# Hoov_Fuzz.net
KiCad netlist of a schematic drawn in EAGLE
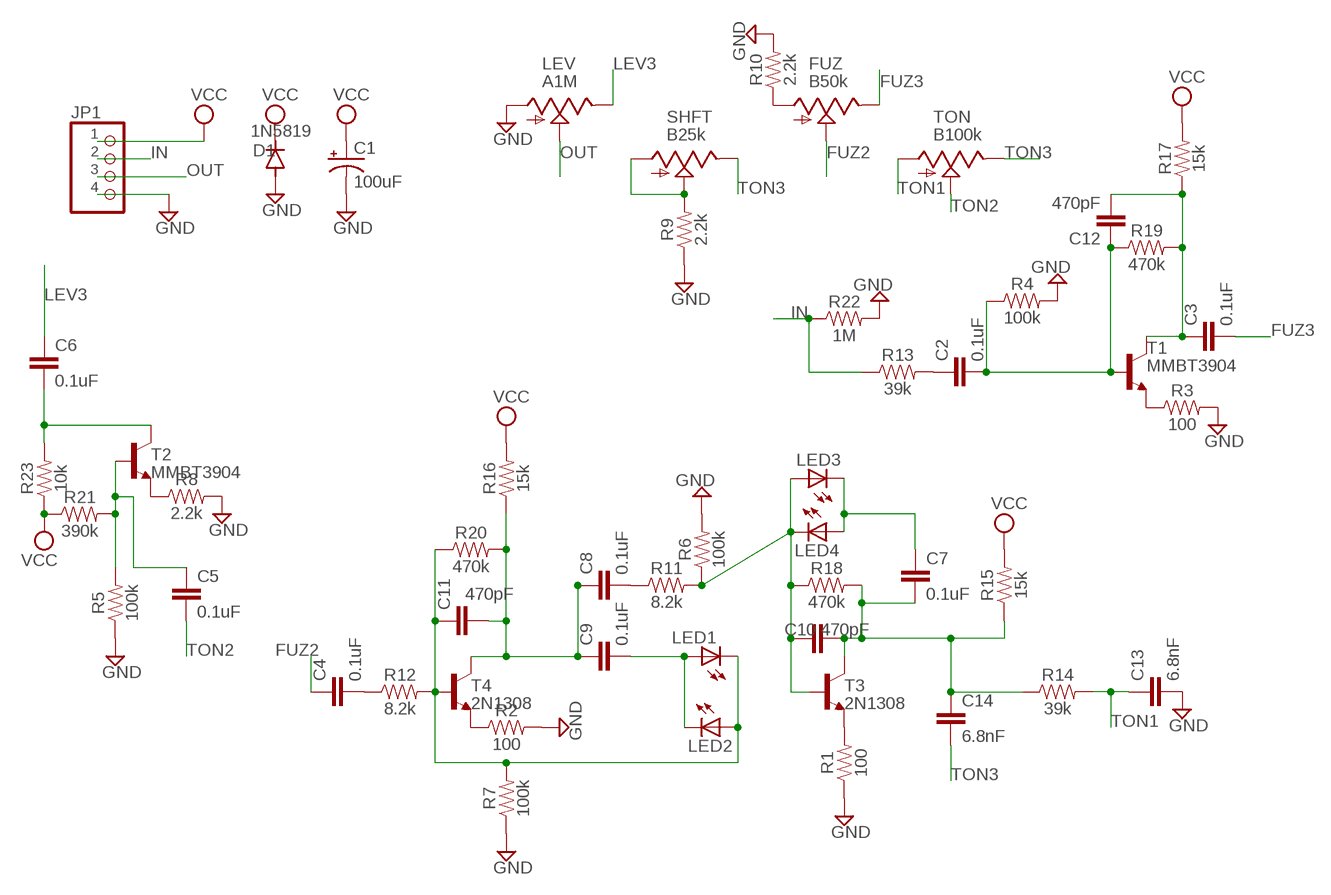
[diagram p0: schematic, sheet 1]

(export (version "E")
  (design (tool "Eeschema 10.0.6"))
  (components
    (comp (ref "C1")
      (value "100uF")
      (footprint "eagle-import:PAN_B_SMD+THRU")
      (libsource (lib "eagle-import") (part "CAP_SMD+THRUPAN_B"))
    )
    (comp (ref "C2")
      (value "0.1uF")
      (footprint "eagle-import:0603")
      (libsource (lib "eagle-import") (part "0.1UF-0603-25V-(+80/-20%)"))
    )
    (comp (ref "C3")
      (value "0.1uF")
      (footprint "eagle-import:0603")
      (libsource (lib "eagle-import") (part "0.1UF-0603-25V-(+80/-20%)"))
    )
    (comp (ref "C4")
      (value "0.1uF")
      (footprint "eagle-import:0603")
      (libsource (lib "eagle-import") (part "0.1UF-0603-25V-(+80/-20%)"))
    )
    (comp (ref "C5")
      (value "0.1uF")
      (footprint "eagle-import:0603")
      (libsource (lib "eagle-import") (part "0.1UF-0603-25V-(+80/-20%)"))
    )
    (comp (ref "C6")
      (value "0.1uF")
      (footprint "eagle-import:0603")
      (libsource (lib "eagle-import") (part "0.1UF-0603-25V-(+80/-20%)"))
    )
    (comp (ref "C7")
      (value "0.1uF")
      (footprint "eagle-import:0603")
      (libsource (lib "eagle-import") (part "0.1UF-0603-25V-(+80/-20%)"))
    )
    (comp (ref "C8")
      (value "0.1uF")
      (footprint "eagle-import:0603")
      (libsource (lib "eagle-import") (part "0.1UF-0603-25V-(+80/-20%)"))
    )
    (comp (ref "C9")
      (value "0.1uF")
      (footprint "eagle-import:0603")
      (libsource (lib "eagle-import") (part "0.1UF-0603-25V-(+80/-20%)"))
    )
    (comp (ref "C10")
      (value "470pF")
      (footprint "eagle-import:0603")
      (libsource (lib "eagle-import") (part "470PF-0603-50V-5%"))
    )
    (comp (ref "C11")
      (value "470pF")
      (footprint "eagle-import:0603")
      (libsource (lib "eagle-import") (part "470PF-0603-50V-5%"))
    )
    (comp (ref "C12")
      (value "470pF")
      (footprint "eagle-import:0603")
      (libsource (lib "eagle-import") (part "470PF-0603-50V-5%"))
    )
    (comp (ref "C13")
      (value "6.8nF")
      (footprint "eagle-import:0603")
      (libsource (lib "eagle-import") (part "470PF-0603-50V-5%"))
    )
    (comp (ref "C14")
      (value "6.8nF")
      (footprint "eagle-import:0603")
      (libsource (lib "eagle-import") (part "470PF-0603-50V-5%"))
    )
    (comp (ref "D1")
      (value "1N5819")
      (footprint "eagle-import:SOD123")
      (libsource (lib "eagle-import") (part "DIODE-SOD123"))
    )
    (comp (ref "FUZ")
      (value "B50k")
      (footprint "eagle-import:9MM_SNAP-IN_POT")
      (libsource (lib "eagle-import") (part "9MM_SNAP-IN_POT_"))
    )
    (comp (ref "JP1")
      (value "PINHD-1X4")
      (footprint "eagle-import:1X04")
      (libsource (lib "eagle-import") (part "PINHD-1X4"))
    )
    (comp (ref "LED1")
      (value "LED_E")
      (footprint "eagle-import:LED_1206")
      (libsource (lib "eagle-import") (part "LED_E"))
    )
    (comp (ref "LED2")
      (value "LED_E")
      (footprint "eagle-import:LED_1206")
      (libsource (lib "eagle-import") (part "LED_E"))
    )
    (comp (ref "LED3")
      (value "LED_E")
      (footprint "eagle-import:LED_1206")
      (libsource (lib "eagle-import") (part "LED_E"))
    )
    (comp (ref "LED4")
      (value "LED_E")
      (footprint "eagle-import:LED_1206")
      (libsource (lib "eagle-import") (part "LED_E"))
    )
    (comp (ref "LEV")
      (value "A1M")
      (footprint "eagle-import:9MM_SNAP-IN_POT")
      (libsource (lib "eagle-import") (part "9MM_SNAP-IN_POT_"))
    )
    (comp (ref "R1")
      (value "100")
      (footprint "eagle-import:0603")
      (libsource (lib "eagle-import") (part "100OHM-0603-1/4W-5%"))
    )
    (comp (ref "R2")
      (value "100")
      (footprint "eagle-import:0603")
      (libsource (lib "eagle-import") (part "100OHM-0603-1/4W-5%"))
    )
    (comp (ref "R3")
      (value "100")
      (footprint "eagle-import:0603")
      (libsource (lib "eagle-import") (part "100OHM-0603-1/4W-5%"))
    )
    (comp (ref "R4")
      (value "100k")
      (footprint "eagle-import:0603")
      (libsource (lib "eagle-import") (part "100KOHM-0603-1/10W-1%"))
    )
    (comp (ref "R5")
      (value "100k")
      (footprint "eagle-import:0603")
      (libsource (lib "eagle-import") (part "100KOHM-0603-1/10W-1%"))
    )
    (comp (ref "R6")
      (value "100k")
      (footprint "eagle-import:0603")
      (libsource (lib "eagle-import") (part "100KOHM-0603-1/10W-1%"))
    )
    (comp (ref "R7")
      (value "100k")
      (footprint "eagle-import:0603")
      (libsource (lib "eagle-import") (part "100KOHM-0603-1/10W-1%"))
    )
    (comp (ref "R8")
      (value "2.2k")
      (footprint "eagle-import:0603")
      (libsource (lib "eagle-import") (part "2.2KOHM-0603-1/10W-1%"))
    )
    (comp (ref "R9")
      (value "2.2k")
      (footprint "eagle-import:0603")
      (libsource (lib "eagle-import") (part "2.2KOHM-0603-1/10W-1%"))
    )
    (comp (ref "R10")
      (value "2.2k")
      (footprint "eagle-import:0603")
      (libsource (lib "eagle-import") (part "2.2KOHM-0603-1/10W-1%"))
    )
    (comp (ref "R11")
      (value "8.2k")
      (footprint "eagle-import:0603")
      (libsource (lib "eagle-import") (part "8.2KOHM-0603-1/10W-5%"))
    )
    (comp (ref "R12")
      (value "8.2k")
      (footprint "eagle-import:0603")
      (libsource (lib "eagle-import") (part "8.2KOHM-0603-1/10W-5%"))
    )
    (comp (ref "R13")
      (value "39k")
      (footprint "eagle-import:0603")
      (libsource (lib "eagle-import") (part "39KOHM-0603-1/10W-1%"))
    )
    (comp (ref "R14")
      (value "39k")
      (footprint "eagle-import:0603")
      (libsource (lib "eagle-import") (part "39KOHM-0603-1/10W-1%"))
    )
    (comp (ref "R15")
      (value "15k")
      (footprint "eagle-import:0603")
      (libsource (lib "eagle-import") (part "15KOHM-0603-1/10W-1%"))
    )
    (comp (ref "R16")
      (value "15k")
      (footprint "eagle-import:0603")
      (libsource (lib "eagle-import") (part "15KOHM-0603-1/10W-1%"))
    )
    (comp (ref "R17")
      (value "15k")
      (footprint "eagle-import:0603")
      (libsource (lib "eagle-import") (part "15KOHM-0603-1/10W-1%"))
    )
    (comp (ref "R18")
      (value "470k")
      (footprint "eagle-import:0603")
      (libsource (lib "eagle-import") (part "RESISTOR0603"))
    )
    (comp (ref "R19")
      (value "470k")
      (footprint "eagle-import:0603")
      (libsource (lib "eagle-import") (part "RESISTOR0603"))
    )
    (comp (ref "R20")
      (value "470k")
      (footprint "eagle-import:0603")
      (libsource (lib "eagle-import") (part "RESISTOR0603"))
    )
    (comp (ref "R21")
      (value "390k")
      (footprint "eagle-import:0603")
      (libsource (lib "eagle-import") (part "390KOHM-0603-1/10W-1%"))
    )
    (comp (ref "R22")
      (value "1M")
      (footprint "eagle-import:0603")
      (libsource (lib "eagle-import") (part "1MOHM-0603-1/4W-5%"))
    )
    (comp (ref "R23")
      (value "10k")
      (footprint "eagle-import:0603")
      (libsource (lib "eagle-import") (part "10KOHM-0603-1/10W-1%"))
    )
    (comp (ref "SHFT")
      (value "B25k")
      (footprint "eagle-import:9MM_SNAP-IN_POT")
      (libsource (lib "eagle-import") (part "9MM_SNAP-IN_POT_"))
    )
    (comp (ref "T1")
      (value "MMBT3904")
      (footprint "eagle-import:SOT23-BEC")
      (libsource (lib "eagle-import") (part "-NPN-SOT23-BECBC817-16LT1"))
    )
    (comp (ref "T2")
      (value "MMBT3904")
      (footprint "eagle-import:SOT23-BEC")
      (libsource (lib "eagle-import") (part "-NPN-SOT23-BECBC817-16LT1"))
    )
    (comp (ref "T3")
      (value "2N1308")
      (footprint "eagle-import:TO5")
      (libsource (lib "eagle-import") (part "-NPN-TO5"))
    )
    (comp (ref "T4")
      (value "2N1308")
      (footprint "eagle-import:TO5")
      (libsource (lib "eagle-import") (part "-NPN-TO5"))
    )
    (comp (ref "TON")
      (value "B100k")
      (footprint "eagle-import:9MM_SNAP-IN_POT")
      (libsource (lib "eagle-import") (part "9MM_SNAP-IN_POT_"))
    )
  )
  (nets
    (net (code "1") (name "/FUZ2") (class "Default")
      (node (ref "C4") (pin "1") (pinfunction "1_1") (pintype "passive"))
      (node (ref "FUZ") (pin "2") (pinfunction "S_2") (pintype "passive"))
    )
    (net (code "2") (name "/FUZ3") (class "Default")
      (node (ref "C3") (pin "2") (pinfunction "2_2") (pintype "passive"))
      (node (ref "FUZ") (pin "3") (pinfunction "E_3") (pintype "passive"))
    )
    (net (code "3") (name "/IN") (class "Default")
      (node (ref "JP1") (pin "2") (pinfunction "2_2") (pintype "passive"))
      (node (ref "R13") (pin "1") (pinfunction "1_1") (pintype "passive"))
      (node (ref "R22") (pin "1") (pinfunction "1_1") (pintype "passive"))
    )
    (net (code "4") (name "/LEV3") (class "Default")
      (node (ref "C6") (pin "1") (pinfunction "1_1") (pintype "passive"))
      (node (ref "LEV") (pin "3") (pinfunction "E_3") (pintype "passive"))
    )
    (net (code "5") (name "/OUT") (class "Default")
      (node (ref "JP1") (pin "3") (pinfunction "3_3") (pintype "passive"))
      (node (ref "LEV") (pin "2") (pinfunction "S_2") (pintype "passive"))
    )
    (net (code "6") (name "/TON1") (class "Default")
      (node (ref "C13") (pin "1") (pinfunction "1_1") (pintype "passive"))
      (node (ref "R14") (pin "2") (pinfunction "2_2") (pintype "passive"))
      (node (ref "TON") (pin "1") (pinfunction "A_1") (pintype "passive"))
    )
    (net (code "7") (name "/TON2") (class "Default")
      (node (ref "C5") (pin "2") (pinfunction "2_2") (pintype "passive"))
      (node (ref "TON") (pin "2") (pinfunction "S_2") (pintype "passive"))
    )
    (net (code "8") (name "/TON3") (class "Default")
      (node (ref "C14") (pin "2") (pinfunction "2_2") (pintype "passive"))
      (node (ref "SHFT") (pin "3") (pinfunction "E_3") (pintype "passive"))
      (node (ref "TON") (pin "3") (pinfunction "E_3") (pintype "passive"))
    )
    (net (code "9") (name "GND") (class "Default")
      (node (ref "C1") (pin "-") (pinfunction "-_-") (pintype "passive"))
      (node (ref "C1") (pin "--") (pinfunction "-_--") (pintype "passive"))
      (node (ref "C13") (pin "2") (pinfunction "2_2") (pintype "passive"))
      (node (ref "D1") (pin "A") (pinfunction "A_A") (pintype "passive"))
      (node (ref "JP1") (pin "4") (pinfunction "4_4") (pintype "passive"))
      (node (ref "LEV") (pin "1") (pinfunction "A_1") (pintype "passive"))
      (node (ref "R1") (pin "1") (pinfunction "1_1") (pintype "passive"))
      (node (ref "R10") (pin "2") (pinfunction "2_2") (pintype "passive"))
      (node (ref "R2") (pin "2") (pinfunction "2_2") (pintype "passive"))
      (node (ref "R22") (pin "2") (pinfunction "2_2") (pintype "passive"))
      (node (ref "R3") (pin "2") (pinfunction "2_2") (pintype "passive"))
      (node (ref "R4") (pin "2") (pinfunction "2_2") (pintype "passive"))
      (node (ref "R5") (pin "1") (pinfunction "1_1") (pintype "passive"))
      (node (ref "R6") (pin "2") (pinfunction "2_2") (pintype "passive"))
      (node (ref "R7") (pin "1") (pinfunction "1_1") (pintype "passive"))
      (node (ref "R8") (pin "2") (pinfunction "2_2") (pintype "passive"))
      (node (ref "R9") (pin "1") (pinfunction "1_1") (pintype "passive"))
    )
    (net (code "10") (name "Net-(C2-Pad1)") (class "Default")
      (node (ref "C2") (pin "1") (pinfunction "1_1") (pintype "passive"))
      (node (ref "R13") (pin "2") (pinfunction "2_2") (pintype "passive"))
    )
    (net (code "11") (name "Net-(C4-Pad2)") (class "Default")
      (node (ref "C4") (pin "2") (pinfunction "2_2") (pintype "passive"))
      (node (ref "R12") (pin "1") (pinfunction "1_1") (pintype "passive"))
    )
    (net (code "12") (name "Net-(C5-Pad1)") (class "Default")
      (node (ref "C5") (pin "1") (pinfunction "1_1") (pintype "passive"))
      (node (ref "R21") (pin "2") (pinfunction "2_2") (pintype "passive"))
      (node (ref "R5") (pin "2") (pinfunction "2_2") (pintype "passive"))
      (node (ref "T2") (pin "B") (pinfunction "B_B") (pintype "passive"))
    )
    (net (code "13") (name "Net-(C6-Pad2)") (class "Default")
      (node (ref "C6") (pin "2") (pinfunction "2_2") (pintype "passive"))
      (node (ref "R23") (pin "2") (pinfunction "2_2") (pintype "passive"))
      (node (ref "T2") (pin "C") (pinfunction "C_C") (pintype "passive"))
    )
    (net (code "14") (name "Net-(C7-Pad1)") (class "Default")
      (node (ref "C7") (pin "1") (pinfunction "1_1") (pintype "passive"))
      (node (ref "LED3") (pin "C") (pinfunction "C_C") (pintype "passive"))
      (node (ref "LED4") (pin "A") (pinfunction "A_A") (pintype "passive"))
    )
    (net (code "15") (name "Net-(C8-Pad2)") (class "Default")
      (node (ref "C8") (pin "2") (pinfunction "2_2") (pintype "passive"))
      (node (ref "R11") (pin "1") (pinfunction "1_1") (pintype "passive"))
    )
    (net (code "16") (name "Net-(C9-Pad2)") (class "Default")
      (node (ref "C9") (pin "2") (pinfunction "2_2") (pintype "passive"))
      (node (ref "LED1") (pin "A") (pinfunction "A_A") (pintype "passive"))
      (node (ref "LED2") (pin "C") (pinfunction "C_C") (pintype "passive"))
    )
    (net (code "17") (name "Net-(C12-Pad1)") (class "Default")
      (node (ref "C12") (pin "1") (pinfunction "1_1") (pintype "passive"))
      (node (ref "C2") (pin "2") (pinfunction "2_2") (pintype "passive"))
      (node (ref "R19") (pin "1") (pinfunction "1_1") (pintype "passive"))
      (node (ref "R4") (pin "1") (pinfunction "1_1") (pintype "passive"))
      (node (ref "T1") (pin "B") (pinfunction "B_B") (pintype "passive"))
    )
    (net (code "18") (name "Net-(C12-Pad2)") (class "Default")
      (node (ref "C12") (pin "2") (pinfunction "2_2") (pintype "passive"))
      (node (ref "C3") (pin "1") (pinfunction "1_1") (pintype "passive"))
      (node (ref "R17") (pin "1") (pinfunction "1_1") (pintype "passive"))
      (node (ref "R19") (pin "2") (pinfunction "2_2") (pintype "passive"))
      (node (ref "T1") (pin "C") (pinfunction "C_C") (pintype "passive"))
    )
    (net (code "19") (name "Net-(FUZ-A)") (class "Default")
      (node (ref "FUZ") (pin "1") (pinfunction "A_1") (pintype "passive"))
      (node (ref "R10") (pin "1") (pinfunction "1_1") (pintype "passive"))
    )
    (net (code "20") (name "Net-(R3-Pad1)") (class "Default")
      (node (ref "R3") (pin "1") (pinfunction "1_1") (pintype "passive"))
      (node (ref "T1") (pin "E") (pinfunction "E_E") (pintype "passive"))
    )
    (net (code "21") (name "Net-(R8-Pad1)") (class "Default")
      (node (ref "R8") (pin "1") (pinfunction "1_1") (pintype "passive"))
      (node (ref "T2") (pin "E") (pinfunction "E_E") (pintype "passive"))
    )
    (net (code "22") (name "Net-(SHFT-A)") (class "Default")
      (node (ref "R9") (pin "2") (pinfunction "2_2") (pintype "passive"))
      (node (ref "SHFT") (pin "1") (pinfunction "A_1") (pintype "passive"))
      (node (ref "SHFT") (pin "2") (pinfunction "S_2") (pintype "passive"))
    )
    (net (code "23") (name "Net-(T3-B)") (class "Default")
      (node (ref "C10") (pin "1") (pinfunction "1_1") (pintype "passive"))
      (node (ref "LED3") (pin "A") (pinfunction "A_A") (pintype "passive"))
      (node (ref "LED4") (pin "C") (pinfunction "C_C") (pintype "passive"))
      (node (ref "R11") (pin "2") (pinfunction "2_2") (pintype "passive"))
      (node (ref "R18") (pin "1") (pinfunction "1_1") (pintype "passive"))
      (node (ref "R6") (pin "1") (pinfunction "1_1") (pintype "passive"))
      (node (ref "T3") (pin "2") (pinfunction "B_2") (pintype "passive"))
    )
    (net (code "24") (name "Net-(T3-C)") (class "Default")
      (node (ref "C10") (pin "2") (pinfunction "2_2") (pintype "passive"))
      (node (ref "C14") (pin "1") (pinfunction "1_1") (pintype "passive"))
      (node (ref "C7") (pin "2") (pinfunction "2_2") (pintype "passive"))
      (node (ref "R14") (pin "1") (pinfunction "1_1") (pintype "passive"))
      (node (ref "R15") (pin "1") (pinfunction "1_1") (pintype "passive"))
      (node (ref "R18") (pin "2") (pinfunction "2_2") (pintype "passive"))
      (node (ref "T3") (pin "3") (pinfunction "C_3") (pintype "passive"))
    )
    (net (code "25") (name "Net-(T3-E)") (class "Default")
      (node (ref "R1") (pin "2") (pinfunction "2_2") (pintype "passive"))
      (node (ref "T3") (pin "1") (pinfunction "E_1") (pintype "passive"))
    )
    (net (code "26") (name "Net-(T4-B)") (class "Default")
      (node (ref "C11") (pin "1") (pinfunction "1_1") (pintype "passive"))
      (node (ref "LED1") (pin "C") (pinfunction "C_C") (pintype "passive"))
      (node (ref "LED2") (pin "A") (pinfunction "A_A") (pintype "passive"))
      (node (ref "R12") (pin "2") (pinfunction "2_2") (pintype "passive"))
      (node (ref "R20") (pin "1") (pinfunction "1_1") (pintype "passive"))
      (node (ref "R7") (pin "2") (pinfunction "2_2") (pintype "passive"))
      (node (ref "T4") (pin "2") (pinfunction "B_2") (pintype "passive"))
    )
    (net (code "27") (name "Net-(T4-C)") (class "Default")
      (node (ref "C11") (pin "2") (pinfunction "2_2") (pintype "passive"))
      (node (ref "C8") (pin "1") (pinfunction "1_1") (pintype "passive"))
      (node (ref "C9") (pin "1") (pinfunction "1_1") (pintype "passive"))
      (node (ref "R16") (pin "1") (pinfunction "1_1") (pintype "passive"))
      (node (ref "R20") (pin "2") (pinfunction "2_2") (pintype "passive"))
      (node (ref "T4") (pin "3") (pinfunction "C_3") (pintype "passive"))
    )
    (net (code "28") (name "Net-(T4-E)") (class "Default")
      (node (ref "R2") (pin "1") (pinfunction "1_1") (pintype "passive"))
      (node (ref "T4") (pin "1") (pinfunction "E_1") (pintype "passive"))
    )
    (net (code "29") (name "VCC") (class "Default")
      (node (ref "C1") (pin "+") (pinfunction "+_+") (pintype "passive"))
      (node (ref "C1") (pin "++") (pinfunction "+_++") (pintype "passive"))
      (node (ref "D1") (pin "C") (pinfunction "C_C") (pintype "passive"))
      (node (ref "JP1") (pin "1") (pinfunction "1_1") (pintype "passive"))
      (node (ref "R15") (pin "2") (pinfunction "2_2") (pintype "passive"))
      (node (ref "R16") (pin "2") (pinfunction "2_2") (pintype "passive"))
      (node (ref "R17") (pin "2") (pinfunction "2_2") (pintype "passive"))
      (node (ref "R21") (pin "1") (pinfunction "1_1") (pintype "passive"))
      (node (ref "R23") (pin "1") (pinfunction "1_1") (pintype "passive"))
    )
  )
)
